# BigTimeBottom.net
KiCad netlist of a schematic drawn in EAGLE
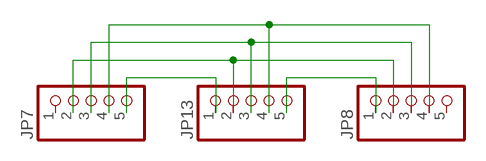
[diagram p0: schematic, sheet 1]

(export (version "E")
  (design (tool "Eeschema 10.0.6"))
  (components
    (comp (ref "JP7")
      (value "HEADER-1X576MIL")
      (footprint "eagle-import:1X05_ROUND_76")
      (libsource (lib "eagle-import") (part "HEADER-1X576MIL"))
    )
    (comp (ref "JP8")
      (value "HEADER-1X576MIL")
      (footprint "eagle-import:1X05_ROUND_76")
      (libsource (lib "eagle-import") (part "HEADER-1X576MIL"))
    )
    (comp (ref "JP13")
      (value "HEADER-1X576MIL")
      (footprint "eagle-import:1X05_ROUND_76")
      (libsource (lib "eagle-import") (part "HEADER-1X576MIL"))
    )
  )
  (nets
    (net (code "1") (name "Net-(JP13-Pad1)") (class "Default")
      (node (ref "JP13") (pin "1") (pinfunction "1_1") (pintype "passive"))
      (node (ref "JP7") (pin "5") (pinfunction "5_5") (pintype "passive"))
    )
    (net (code "2") (name "Net-(JP13-Pad2)") (class "Default")
      (node (ref "JP13") (pin "2") (pinfunction "2_2") (pintype "passive"))
      (node (ref "JP7") (pin "2") (pinfunction "2_2") (pintype "passive"))
      (node (ref "JP8") (pin "2") (pinfunction "2_2") (pintype "passive"))
    )
    (net (code "3") (name "Net-(JP13-Pad3)") (class "Default")
      (node (ref "JP13") (pin "3") (pinfunction "3_3") (pintype "passive"))
      (node (ref "JP7") (pin "3") (pinfunction "3_3") (pintype "passive"))
      (node (ref "JP8") (pin "3") (pinfunction "3_3") (pintype "passive"))
    )
    (net (code "4") (name "Net-(JP13-Pad4)") (class "Default")
      (node (ref "JP13") (pin "4") (pinfunction "4_4") (pintype "passive"))
      (node (ref "JP7") (pin "4") (pinfunction "4_4") (pintype "passive"))
      (node (ref "JP8") (pin "4") (pinfunction "4_4") (pintype "passive"))
    )
    (net (code "5") (name "Net-(JP13-Pad5)") (class "Default")
      (node (ref "JP13") (pin "5") (pinfunction "5_5") (pintype "passive"))
      (node (ref "JP8") (pin "1") (pinfunction "1_1") (pintype "passive"))
    )
    (net (code "6") (name "unconnected-(JP7-Pad1)") (class "Default")
      (node (ref "JP7") (pin "1") (pinfunction "1_1") (pintype "passive"))
    )
    (net (code "7") (name "unconnected-(JP8-Pad5)") (class "Default")
      (node (ref "JP8") (pin "5") (pinfunction "5_5") (pintype "passive"))
    )
  )
)
